# m1-mar.net
KiCad netlist of a schematic drawn in EAGLE
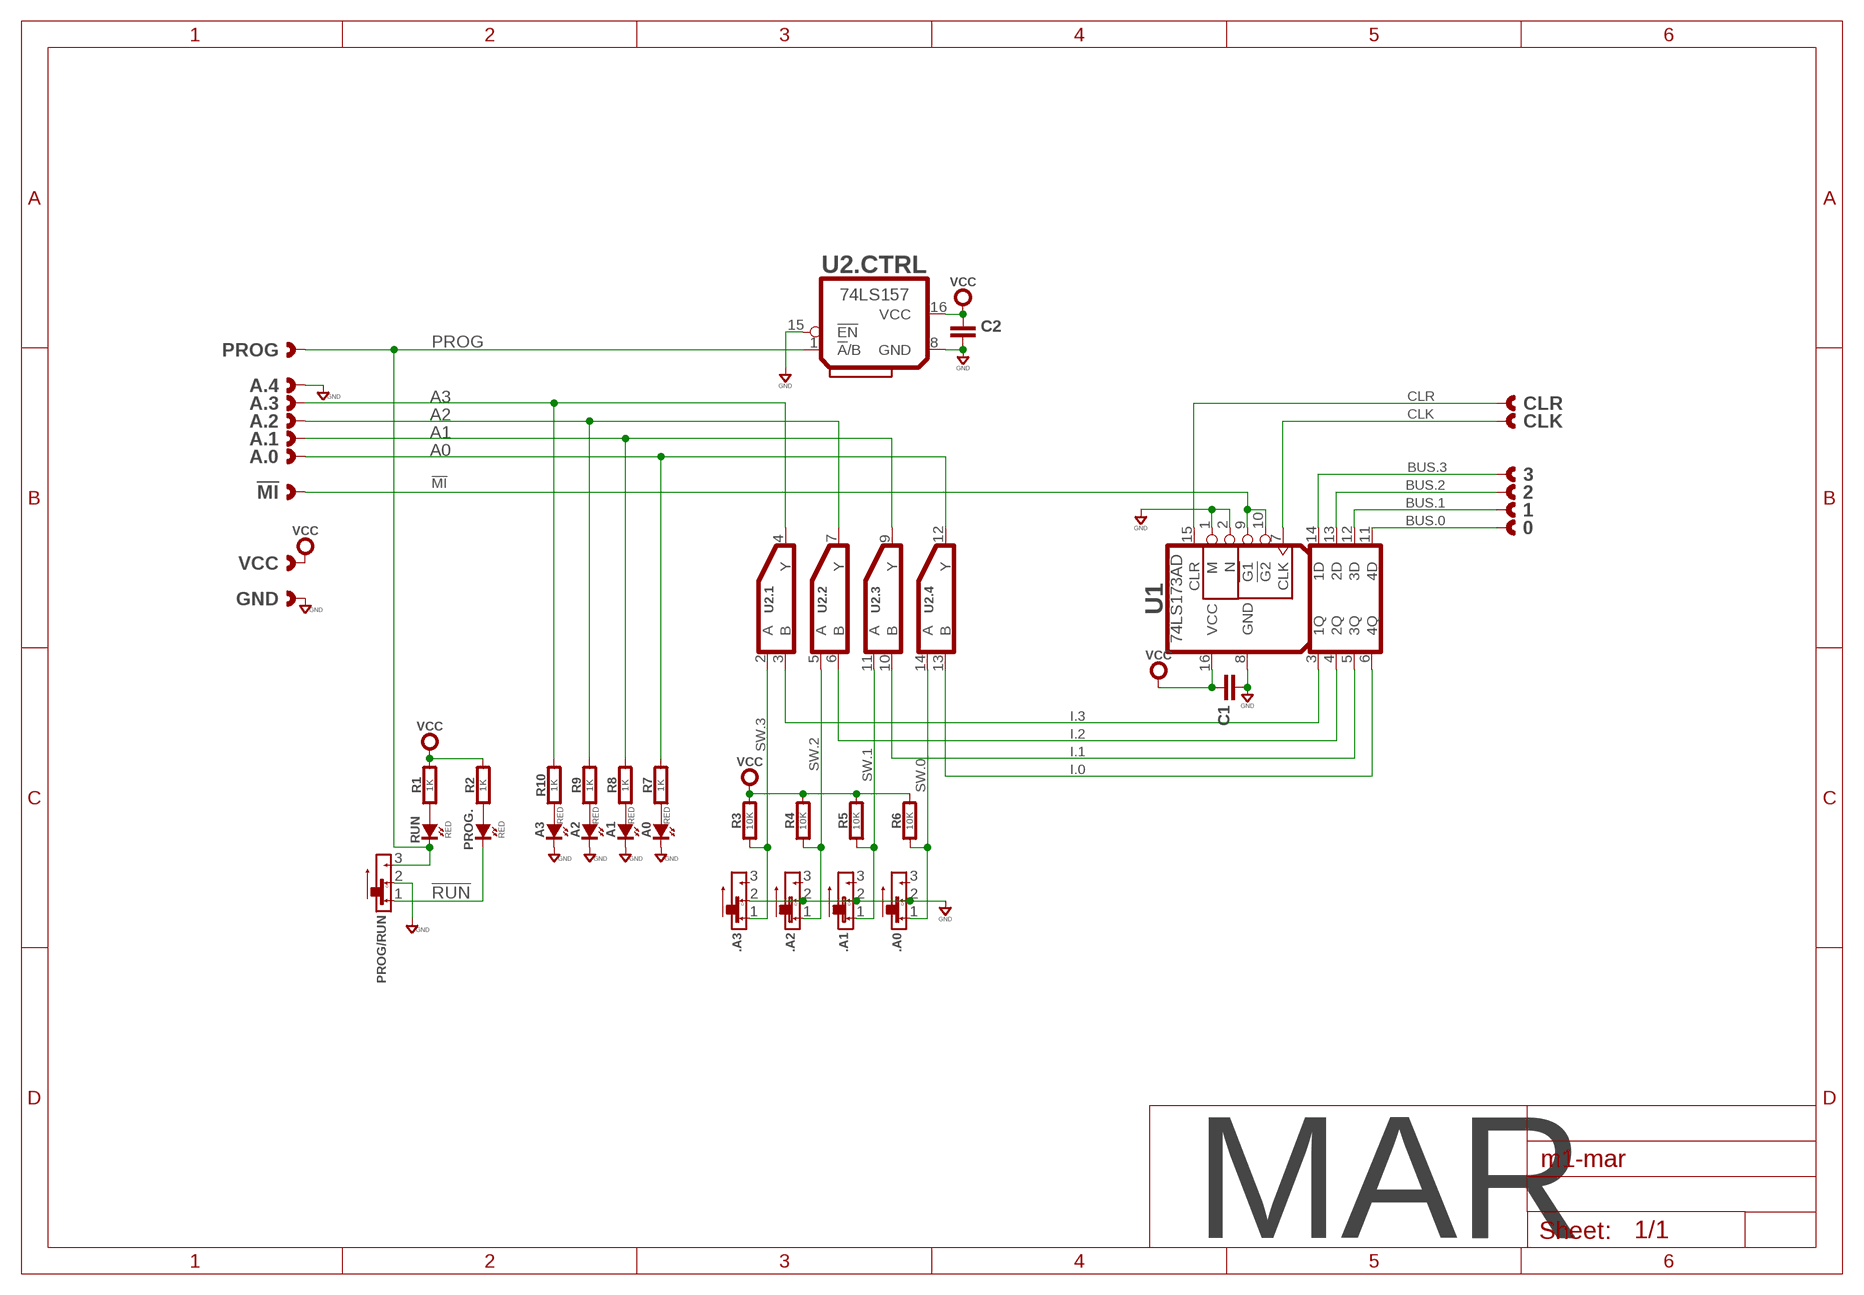
[diagram p0: schematic, sheet 1]

(export (version "E")
  (design (tool "Eeschema 10.0.6"))
  (components
    (comp (ref "!MI")
      (value "CAST-01X1")
      (footprint "eagle-import:CAST01-2.54MM")
      (libsource (lib "eagle-import") (part "CAST-01X1"))
    )
    (comp (ref ".A0")
      (value "SLIDE-SPDTJS102011JCQN")
      (footprint "eagle-import:CK_JS102011JCQN")
      (libsource (lib "eagle-import") (part "SLIDE-SPDTJS102011JCQN"))
    )
    (comp (ref ".A1")
      (value "SLIDE-SPDTJS102011JCQN")
      (footprint "eagle-import:CK_JS102011JCQN")
      (libsource (lib "eagle-import") (part "SLIDE-SPDTJS102011JCQN"))
    )
    (comp (ref ".A2")
      (value "SLIDE-SPDTJS102011JCQN")
      (footprint "eagle-import:CK_JS102011JCQN")
      (libsource (lib "eagle-import") (part "SLIDE-SPDTJS102011JCQN"))
    )
    (comp (ref ".A3")
      (value "SLIDE-SPDTJS102011JCQN")
      (footprint "eagle-import:CK_JS102011JCQN")
      (libsource (lib "eagle-import") (part "SLIDE-SPDTJS102011JCQN"))
    )
    (comp (ref "0")
      (value "CAST-01X1")
      (footprint "eagle-import:CAST01-2.54MM")
      (libsource (lib "eagle-import") (part "CAST-01X1"))
    )
    (comp (ref "1")
      (value "CAST-01X1")
      (footprint "eagle-import:CAST01-2.54MM")
      (libsource (lib "eagle-import") (part "CAST-01X1"))
    )
    (comp (ref "2")
      (value "CAST-01X1")
      (footprint "eagle-import:CAST01-2.54MM")
      (libsource (lib "eagle-import") (part "CAST-01X1"))
    )
    (comp (ref "3")
      (value "CAST-01X1")
      (footprint "eagle-import:CAST01-2.54MM")
      (libsource (lib "eagle-import") (part "CAST-01X1"))
    )
    (comp (ref "A.0")
      (value "CAST-01X1")
      (footprint "eagle-import:CAST01-2.54MM")
      (libsource (lib "eagle-import") (part "CAST-01X1"))
    )
    (comp (ref "A.1")
      (value "CAST-01X1")
      (footprint "eagle-import:CAST01-2.54MM")
      (libsource (lib "eagle-import") (part "CAST-01X1"))
    )
    (comp (ref "A.2")
      (value "CAST-01X1")
      (footprint "eagle-import:CAST01-2.54MM")
      (libsource (lib "eagle-import") (part "CAST-01X1"))
    )
    (comp (ref "A.3")
      (value "CAST-01X1")
      (footprint "eagle-import:CAST01-2.54MM")
      (libsource (lib "eagle-import") (part "CAST-01X1"))
    )
    (comp (ref "A.4")
      (value "CAST-01X1")
      (footprint "eagle-import:CAST01-2.54MM")
      (libsource (lib "eagle-import") (part "CAST-01X1"))
    )
    (comp (ref "A0")
      (value "RED")
      (footprint "eagle-import:SMD_0603")
      (libsource (lib "eagle-import") (part "SMT0603"))
    )
    (comp (ref "A1")
      (value "RED")
      (footprint "eagle-import:SMD_0603")
      (libsource (lib "eagle-import") (part "SMT0603"))
    )
    (comp (ref "A2")
      (value "RED")
      (footprint "eagle-import:SMD_0603")
      (libsource (lib "eagle-import") (part "SMT0603"))
    )
    (comp (ref "A3")
      (value "RED")
      (footprint "eagle-import:SMD_0603")
      (libsource (lib "eagle-import") (part "SMT0603"))
    )
    (comp (ref "C1")
      (value "CAPACITOR0603")
      (footprint "eagle-import:0603-CAP")
      (libsource (lib "eagle-import") (part "CAPACITOR0603"))
    )
    (comp (ref "C2")
      (value "CAPACITOR0603")
      (footprint "eagle-import:0603-CAP")
      (libsource (lib "eagle-import") (part "CAPACITOR0603"))
    )
    (comp (ref "CLK")
      (value "CAST-01X1")
      (footprint "eagle-import:CAST01-2.54MM")
      (libsource (lib "eagle-import") (part "CAST-01X1"))
    )
    (comp (ref "CLR")
      (value "CAST-01X1")
      (footprint "eagle-import:CAST01-2.54MM")
      (libsource (lib "eagle-import") (part "CAST-01X1"))
    )
    (comp (ref "GND")
      (value "CAST-01X1")
      (footprint "eagle-import:CAST01-2.54MM")
      (libsource (lib "eagle-import") (part "CAST-01X1"))
    )
    (comp (ref "PROG")
      (value "CAST-01X1")
      (footprint "eagle-import:CAST01-2.54MM")
      (libsource (lib "eagle-import") (part "CAST-01X1"))
    )
    (comp (ref "PROG.")
      (value "RED")
      (footprint "eagle-import:SMD_0603")
      (libsource (lib "eagle-import") (part "SMT0603"))
    )
    (comp (ref "PROG/RUN")
      (value "SLIDE-SPDTJS102011JCQN")
      (footprint "eagle-import:CK_JS102011JCQN")
      (libsource (lib "eagle-import") (part "SLIDE-SPDTJS102011JCQN"))
    )
    (comp (ref "R1")
      (value "1K")
      (footprint "eagle-import:0603-RES")
      (libsource (lib "eagle-import") (part "RESISTOR0603"))
    )
    (comp (ref "R2")
      (value "1K")
      (footprint "eagle-import:0603-RES")
      (libsource (lib "eagle-import") (part "RESISTOR0603"))
    )
    (comp (ref "R3")
      (value "10K")
      (footprint "eagle-import:0603-RES")
      (libsource (lib "eagle-import") (part "RESISTOR0603"))
    )
    (comp (ref "R4")
      (value "10K")
      (footprint "eagle-import:0603-RES")
      (libsource (lib "eagle-import") (part "RESISTOR0603"))
    )
    (comp (ref "R5")
      (value "10K")
      (footprint "eagle-import:0603-RES")
      (libsource (lib "eagle-import") (part "RESISTOR0603"))
    )
    (comp (ref "R6")
      (value "10K")
      (footprint "eagle-import:0603-RES")
      (libsource (lib "eagle-import") (part "RESISTOR0603"))
    )
    (comp (ref "R7")
      (value "1K")
      (footprint "eagle-import:0603-RES")
      (libsource (lib "eagle-import") (part "RESISTOR0603"))
    )
    (comp (ref "R8")
      (value "1K")
      (footprint "eagle-import:0603-RES")
      (libsource (lib "eagle-import") (part "RESISTOR0603"))
    )
    (comp (ref "R9")
      (value "1K")
      (footprint "eagle-import:0603-RES")
      (libsource (lib "eagle-import") (part "RESISTOR0603"))
    )
    (comp (ref "R10")
      (value "1K")
      (footprint "eagle-import:0603-RES")
      (libsource (lib "eagle-import") (part "RESISTOR0603"))
    )
    (comp (ref "RUN")
      (value "RED")
      (footprint "eagle-import:SMD_0603")
      (libsource (lib "eagle-import") (part "SMT0603"))
    )
    (comp (ref "U1")
      (value "74LS173AD")
      (footprint "eagle-import:SO16")
      (libsource (lib "eagle-import") (part "74173A?DLS"))
    )
    (comp (ref "U2")
      (value "74LS157")
      (footprint "eagle-import:SO16")
      (fields (field (name "MPN") "74LS157D"))
      (libsource (lib "eagle-import") (part "74157?DLS"))
    )
    (comp (ref "VCC")
      (value "CAST-01X1")
      (footprint "eagle-import:CAST01-2.54MM")
      (libsource (lib "eagle-import") (part "CAST-01X1"))
    )
  )
  (nets
    (net (code "1") (name "/A0") (class "Default")
      (node (ref "A.0") (pin "1") (pinfunction "1_1") (pintype "bidirectional"))
      (node (ref "R7") (pin "2") (pinfunction "2_2") (pintype "passive"))
      (node (ref "U2") (pin "12") (pinfunction "Y_12") (pintype "output"))
    )
    (net (code "2") (name "/A1") (class "Default")
      (node (ref "A.1") (pin "1") (pinfunction "1_1") (pintype "bidirectional"))
      (node (ref "R8") (pin "2") (pinfunction "2_2") (pintype "passive"))
      (node (ref "U2") (pin "9") (pinfunction "Y_9") (pintype "output"))
    )
    (net (code "3") (name "/A2") (class "Default")
      (node (ref "A.2") (pin "1") (pinfunction "1_1") (pintype "bidirectional"))
      (node (ref "R9") (pin "2") (pinfunction "2_2") (pintype "passive"))
      (node (ref "U2") (pin "7") (pinfunction "Y_7") (pintype "output"))
    )
    (net (code "4") (name "/A3") (class "Default")
      (node (ref "A.3") (pin "1") (pinfunction "1_1") (pintype "bidirectional"))
      (node (ref "R10") (pin "2") (pinfunction "2_2") (pintype "passive"))
      (node (ref "U2") (pin "4") (pinfunction "Y_4") (pintype "output"))
    )
    (net (code "5") (name "/BUS.0") (class "Default")
      (node (ref "0") (pin "1") (pinfunction "1_1") (pintype "bidirectional"))
      (node (ref "U1") (pin "11") (pinfunction "4D_11") (pintype "bidirectional"))
    )
    (net (code "6") (name "/BUS.1") (class "Default")
      (node (ref "1") (pin "1") (pinfunction "1_1") (pintype "bidirectional"))
      (node (ref "U1") (pin "12") (pinfunction "3D_12") (pintype "bidirectional"))
    )
    (net (code "7") (name "/BUS.2") (class "Default")
      (node (ref "2") (pin "1") (pinfunction "1_1") (pintype "bidirectional"))
      (node (ref "U1") (pin "13") (pinfunction "2D_13") (pintype "bidirectional"))
    )
    (net (code "8") (name "/BUS.3") (class "Default")
      (node (ref "3") (pin "1") (pinfunction "1_1") (pintype "bidirectional"))
      (node (ref "U1") (pin "14") (pinfunction "1D_14") (pintype "bidirectional"))
    )
    (net (code "9") (name "/CLK") (class "Default")
      (node (ref "CLK") (pin "1") (pinfunction "1_1") (pintype "bidirectional"))
      (node (ref "U1") (pin "7") (pinfunction "CLK_7") (pintype "bidirectional"))
    )
    (net (code "10") (name "/CLR") (class "Default")
      (node (ref "CLR") (pin "1") (pinfunction "1_1") (pintype "bidirectional"))
      (node (ref "U1") (pin "15") (pinfunction "CLR_15") (pintype "bidirectional"))
    )
    (net (code "11") (name "/I.0") (class "Default")
      (node (ref "U1") (pin "6") (pinfunction "4Q_6") (pintype "bidirectional"))
      (node (ref "U2") (pin "13") (pinfunction "B_13") (pintype "input"))
    )
    (net (code "12") (name "/I.1") (class "Default")
      (node (ref "U1") (pin "5") (pinfunction "3Q_5") (pintype "bidirectional"))
      (node (ref "U2") (pin "10") (pinfunction "B_10") (pintype "input"))
    )
    (net (code "13") (name "/I.2") (class "Default")
      (node (ref "U1") (pin "4") (pinfunction "2Q_4") (pintype "bidirectional"))
      (node (ref "U2") (pin "6") (pinfunction "B_6") (pintype "input"))
    )
    (net (code "14") (name "/I.3") (class "Default")
      (node (ref "U1") (pin "3") (pinfunction "1Q_3") (pintype "bidirectional"))
      (node (ref "U2") (pin "3") (pinfunction "B_3") (pintype "input"))
    )
    (net (code "15") (name "/PROG") (class "Default")
      (node (ref "PROG") (pin "1") (pinfunction "1_1") (pintype "bidirectional"))
      (node (ref "PROG/RUN") (pin "3") (pinfunction "3_3") (pintype "bidirectional"))
      (node (ref "RUN") (pin "K") (pinfunction "C_K") (pintype "passive"))
      (node (ref "U2") (pin "1") (pinfunction "~{A}/B_1") (pintype "output"))
    )
    (net (code "16") (name "/SW.0") (class "Default")
      (node (ref ".A0") (pin "1") (pinfunction "1_1") (pintype "bidirectional"))
      (node (ref "R6") (pin "1") (pinfunction "1_1") (pintype "passive"))
      (node (ref "U2") (pin "14") (pinfunction "A_14") (pintype "input"))
    )
    (net (code "17") (name "/SW.1") (class "Default")
      (node (ref ".A1") (pin "1") (pinfunction "1_1") (pintype "bidirectional"))
      (node (ref "R5") (pin "1") (pinfunction "1_1") (pintype "passive"))
      (node (ref "U2") (pin "11") (pinfunction "A_11") (pintype "input"))
    )
    (net (code "18") (name "/SW.2") (class "Default")
      (node (ref ".A2") (pin "1") (pinfunction "1_1") (pintype "bidirectional"))
      (node (ref "R4") (pin "1") (pinfunction "1_1") (pintype "passive"))
      (node (ref "U2") (pin "5") (pinfunction "A_5") (pintype "input"))
    )
    (net (code "19") (name "/SW.3") (class "Default")
      (node (ref ".A3") (pin "1") (pinfunction "1_1") (pintype "bidirectional"))
      (node (ref "R3") (pin "1") (pinfunction "1_1") (pintype "passive"))
      (node (ref "U2") (pin "2") (pinfunction "A_2") (pintype "input"))
    )
    (net (code "20") (name "/~{MI}") (class "Default")
      (node (ref "!MI") (pin "1") (pinfunction "1_1") (pintype "bidirectional"))
      (node (ref "U1") (pin "10") (pinfunction "~{G2}_10") (pintype "bidirectional"))
      (node (ref "U1") (pin "9") (pinfunction "~{G1}_9") (pintype "bidirectional"))
    )
    (net (code "21") (name "/~{RUN}") (class "Default")
      (node (ref "PROG.") (pin "K") (pinfunction "C_K") (pintype "passive"))
      (node (ref "PROG/RUN") (pin "1") (pinfunction "1_1") (pintype "bidirectional"))
    )
    (net (code "22") (name "GND") (class "Default")
      (node (ref ".A0") (pin "2") (pinfunction "2_2") (pintype "bidirectional"))
      (node (ref ".A1") (pin "2") (pinfunction "2_2") (pintype "bidirectional"))
      (node (ref ".A2") (pin "2") (pinfunction "2_2") (pintype "bidirectional"))
      (node (ref ".A3") (pin "2") (pinfunction "2_2") (pintype "bidirectional"))
      (node (ref "A.4") (pin "1") (pinfunction "1_1") (pintype "bidirectional"))
      (node (ref "A0") (pin "K") (pinfunction "C_K") (pintype "passive"))
      (node (ref "A1") (pin "K") (pinfunction "C_K") (pintype "passive"))
      (node (ref "A2") (pin "K") (pinfunction "C_K") (pintype "passive"))
      (node (ref "A3") (pin "K") (pinfunction "C_K") (pintype "passive"))
      (node (ref "C1") (pin "2") (pinfunction "2_2") (pintype "passive"))
      (node (ref "C2") (pin "2") (pinfunction "2_2") (pintype "passive"))
      (node (ref "GND") (pin "1") (pinfunction "1_1") (pintype "bidirectional"))
      (node (ref "PROG/RUN") (pin "2") (pinfunction "2_2") (pintype "bidirectional"))
      (node (ref "U1") (pin "1") (pinfunction "M_1") (pintype "bidirectional"))
      (node (ref "U1") (pin "2") (pinfunction "N_2") (pintype "bidirectional"))
      (node (ref "U1") (pin "8") (pinfunction "GND_8") (pintype "bidirectional"))
      (node (ref "U2") (pin "15") (pinfunction "~{EN}_15") (pintype "output"))
      (node (ref "U2") (pin "8") (pinfunction "GND_8") (pintype "power_in"))
    )
    (net (code "23") (name "Net-(A0-PadA)") (class "Default")
      (node (ref "A0") (pin "A") (pinfunction "A_A") (pintype "passive"))
      (node (ref "R7") (pin "1") (pinfunction "1_1") (pintype "passive"))
    )
    (net (code "24") (name "Net-(A1-PadA)") (class "Default")
      (node (ref "A1") (pin "A") (pinfunction "A_A") (pintype "passive"))
      (node (ref "R8") (pin "1") (pinfunction "1_1") (pintype "passive"))
    )
    (net (code "25") (name "Net-(A2-PadA)") (class "Default")
      (node (ref "A2") (pin "A") (pinfunction "A_A") (pintype "passive"))
      (node (ref "R9") (pin "1") (pinfunction "1_1") (pintype "passive"))
    )
    (net (code "26") (name "Net-(A3-PadA)") (class "Default")
      (node (ref "A3") (pin "A") (pinfunction "A_A") (pintype "passive"))
      (node (ref "R10") (pin "1") (pinfunction "1_1") (pintype "passive"))
    )
    (net (code "27") (name "Net-(PROG.-PadA)") (class "Default")
      (node (ref "PROG.") (pin "A") (pinfunction "A_A") (pintype "passive"))
      (node (ref "R2") (pin "1") (pinfunction "1_1") (pintype "passive"))
    )
    (net (code "28") (name "Net-(R1-Pad1)") (class "Default")
      (node (ref "R1") (pin "1") (pinfunction "1_1") (pintype "passive"))
      (node (ref "RUN") (pin "A") (pinfunction "A_A") (pintype "passive"))
    )
    (net (code "29") (name "VCC") (class "Default")
      (node (ref "C1") (pin "1") (pinfunction "1_1") (pintype "passive"))
      (node (ref "C2") (pin "1") (pinfunction "1_1") (pintype "passive"))
      (node (ref "R1") (pin "2") (pinfunction "2_2") (pintype "passive"))
      (node (ref "R2") (pin "2") (pinfunction "2_2") (pintype "passive"))
      (node (ref "R3") (pin "2") (pinfunction "2_2") (pintype "passive"))
      (node (ref "R4") (pin "2") (pinfunction "2_2") (pintype "passive"))
      (node (ref "R5") (pin "2") (pinfunction "2_2") (pintype "passive"))
      (node (ref "R6") (pin "2") (pinfunction "2_2") (pintype "passive"))
      (node (ref "U1") (pin "16") (pinfunction "VCC_16") (pintype "bidirectional"))
      (node (ref "U2") (pin "16") (pinfunction "VCC_16") (pintype "power_in"))
      (node (ref "VCC") (pin "1") (pinfunction "1_1") (pintype "bidirectional"))
    )
    (net (code "30") (name "unconnected-(.A0-Pad3)") (class "Default")
      (node (ref ".A0") (pin "3") (pinfunction "3_3") (pintype "bidirectional"))
    )
    (net (code "31") (name "unconnected-(.A1-Pad3)") (class "Default")
      (node (ref ".A1") (pin "3") (pinfunction "3_3") (pintype "bidirectional"))
    )
    (net (code "32") (name "unconnected-(.A2-Pad3)") (class "Default")
      (node (ref ".A2") (pin "3") (pinfunction "3_3") (pintype "bidirectional"))
    )
    (net (code "33") (name "unconnected-(.A3-Pad3)") (class "Default")
      (node (ref ".A3") (pin "3") (pinfunction "3_3") (pintype "bidirectional"))
    )
  )
)
